# QCopterFC_USB_Sch.net
KiCad netlist of a schematic drawn in Altium Designer
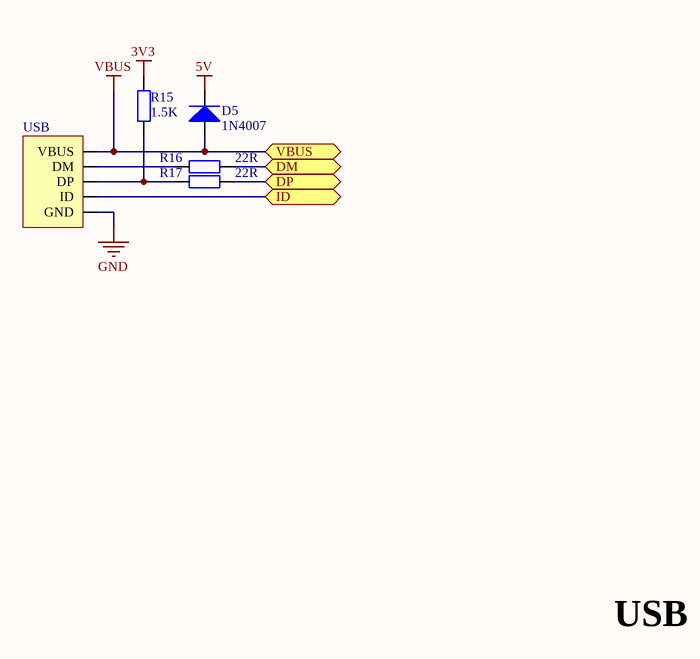
[diagram p0: QCopterFC_USB_Sch.SchDoc]

(export (version "E")
  (design (tool "Eeschema 10.0.6"))
  (components
    (comp (ref "D5")
      (value "Diode_SOD323")
      (footprint "PCB_Active:SOD323")
      (description "Diode")
      (fields (field (name "SOD323") "1N4007"))
      (libsource (lib "SCH_Active") (part "Diode_SOD323"))
    )
    (comp (ref "R15")
      (value "1.5K")
      (footprint "PCB_Passive:RES_0603")
      (description "Resistor")
      (fields (field (name "Comment") "Res_0603"))
      (libsource (lib "") (part "Res_0603_1"))
    )
    (comp (ref "R16")
      (value "22R")
      (footprint "PCB_Passive:RES_0603")
      (description "Resistor")
      (fields (field (name "Comment") "Res_0603"))
      (libsource (lib "SCH_Passive") (part "Res_0603"))
    )
    (comp (ref "R17")
      (value "22R")
      (footprint "PCB_Passive:RES_0603")
      (description "Resistor")
      (fields (field (name "Comment") "Res_0603"))
      (libsource (lib "SCH_Passive") (part "Res_0603"))
    )
    (comp (ref "USB")
      (value "USB_Micro")
      (footprint "PCB_USB:USB_MICRO_B")
      (description "USB")
      (libsource (lib "SCH_USB") (part "USB_Micro"))
    )
  )
  (nets
    (net (code "1") (name "/DM") (class "Default")
      (node (ref "R16") (pin "2") (pinfunction "2_2") (pintype "passive"))
    )
    (net (code "2") (name "/DP") (class "Default")
      (node (ref "R17") (pin "2") (pinfunction "2_2") (pintype "passive"))
    )
    (net (code "3") (name "/ID") (class "Default")
      (node (ref "USB") (pin "4") (pinfunction "ID_4") (pintype "passive"))
    )
    (net (code "4") (name "3V3") (class "Default")
      (node (ref "R15") (pin "2") (pinfunction "2_2") (pintype "passive"))
    )
    (net (code "5") (name "5V") (class "Default")
      (node (ref "D5") (pin "2") (pinfunction "K_2") (pintype "passive"))
    )
    (net (code "6") (name "GND") (class "Default")
      (node (ref "USB") (pin "5") (pinfunction "GND_5") (pintype "passive"))
    )
    (net (code "7") (name "Net-(USB-DM)") (class "Default")
      (node (ref "R16") (pin "1") (pinfunction "1_1") (pintype "passive"))
      (node (ref "USB") (pin "2") (pinfunction "DM_2") (pintype "passive"))
    )
    (net (code "8") (name "Net-(USB-DP)") (class "Default")
      (node (ref "R15") (pin "1") (pinfunction "1_1") (pintype "passive"))
      (node (ref "R17") (pin "1") (pinfunction "1_1") (pintype "passive"))
      (node (ref "USB") (pin "3") (pinfunction "DP_3") (pintype "passive"))
    )
    (net (code "9") (name "VBUS") (class "Default")
      (node (ref "D5") (pin "1") (pinfunction "A_1") (pintype "passive"))
      (node (ref "USB") (pin "1") (pinfunction "VBUS_1") (pintype "passive"))
    )
  )
)
